# monitor.net
KiCad netlist of a schematic drawn in EAGLE
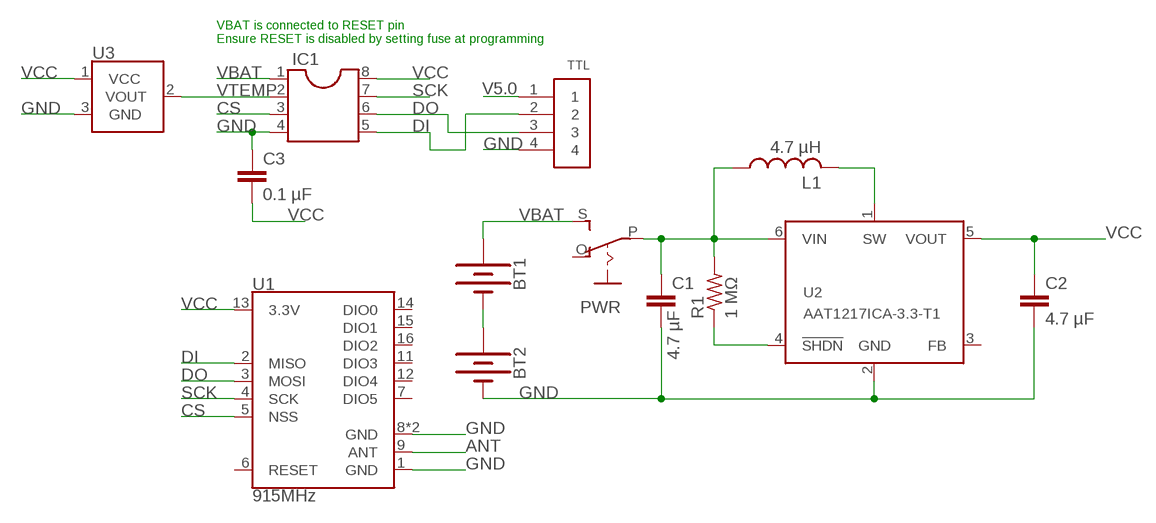
[diagram p0: schematic, sheet 1]

(export (version "E")
  (design (tool "Eeschema 10.0.6"))
  (components
    (comp (ref "BT1")
      (value "BATTERY-AA")
      (footprint "eagle-import:BATTERY-AA")
      (libsource (lib "eagle-import") (part "BATTERY-AA"))
    )
    (comp (ref "BT2")
      (value "BATTERY-AA")
      (footprint "eagle-import:BATTERY-AA")
      (libsource (lib "eagle-import") (part "BATTERY-AA"))
    )
    (comp (ref "C1")
      (value "4.7 µF")
      (footprint "eagle-import:C025-025X050")
      (libsource (lib "eagle-import") (part "C-EU025-025X050"))
    )
    (comp (ref "C2")
      (value "4.7 µF")
      (footprint "eagle-import:C025-025X050")
      (libsource (lib "eagle-import") (part "C-EU025-025X050"))
    )
    (comp (ref "C3")
      (value "0.1 µF")
      (footprint "eagle-import:C025-025X050")
      (libsource (lib "eagle-import") (part "C-EU025-025X050"))
    )
    (comp (ref "IC1")
      (value "DIL8S")
      (footprint "eagle-import:SOCKET-08")
      (libsource (lib "eagle-import") (part "DIL8S"))
    )
    (comp (ref "L1")
      (value "4.7 µH")
      (footprint "eagle-import:0207_12")
      (libsource (lib "eagle-import") (part "L-US0207/12"))
    )
    (comp (ref "PWR")
      (value "EG1218S")
      (footprint "eagle-import:EG1218")
      (libsource (lib "eagle-import") (part "EG1218S"))
    )
    (comp (ref "R1")
      (value "1 MΩ")
      (footprint "eagle-import:0204_5")
      (libsource (lib "eagle-import") (part "R-US_0204/5"))
    )
    (comp (ref "TTL")
      (value "1X4-BIG")
      (footprint "eagle-import:1X04-BIG")
      (libsource (lib "eagle-import") (part "1X4-BIG"))
    )
    (comp (ref "U1")
      (value "915MHz")
      (footprint "eagle-import:RFM69HCW-XXXS2")
      (libsource (lib "eagle-import") (part "RFM69HCW-915"))
    )
    (comp (ref "U2")
      (value "AAT1217ICA-3.3-T1")
      (footprint "eagle-import:TSOT-23-6")
      (libsource (lib "eagle-import") (part "AAT1217ICA-3.3-T1"))
    )
    (comp (ref "U3")
      (value "TMP36GT9")
      (footprint "eagle-import:TO-92")
      (libsource (lib "eagle-import") (part "TMP36GT9"))
    )
  )
  (nets
    (net (code "1") (name "/ANT") (class "Default")
      (node (ref "U1") (pin "9") (pinfunction "ANT_9") (pintype "passive"))
    )
    (net (code "2") (name "/CS") (class "Default")
      (node (ref "IC1") (pin "3") (pinfunction "3_3") (pintype "passive"))
      (node (ref "U1") (pin "5") (pinfunction "NSS_5") (pintype "input"))
    )
    (net (code "3") (name "/DI") (class "Default")
      (node (ref "IC1") (pin "5") (pinfunction "5_5") (pintype "passive"))
      (node (ref "TTL") (pin "2") (pinfunction "2_2") (pintype "bidirectional"))
      (node (ref "U1") (pin "2") (pinfunction "MISO_2") (pintype "bidirectional"))
    )
    (net (code "4") (name "/DO") (class "Default")
      (node (ref "IC1") (pin "6") (pinfunction "6_6") (pintype "passive"))
      (node (ref "TTL") (pin "3") (pinfunction "3_3") (pintype "bidirectional"))
      (node (ref "U1") (pin "3") (pinfunction "MOSI_3") (pintype "input"))
    )
    (net (code "5") (name "/GND") (class "Default")
      (node (ref "BT2") (pin "GND@1") (pinfunction "-_GND@1") (pintype "power_in"))
      (node (ref "C1") (pin "2") (pinfunction "2_2") (pintype "passive"))
      (node (ref "C2") (pin "2") (pinfunction "2_2") (pintype "passive"))
      (node (ref "C3") (pin "1") (pinfunction "1_1") (pintype "passive"))
      (node (ref "IC1") (pin "4") (pinfunction "4_4") (pintype "passive"))
      (node (ref "TTL") (pin "4") (pinfunction "4_4") (pintype "bidirectional"))
      (node (ref "U1") (pin "1") (pinfunction "GND_1") (pintype "power_in"))
      (node (ref "U1") (pin "10") (pinfunction "GND_10") (pintype "power_in"))
      (node (ref "U1") (pin "8") (pinfunction "GND_8") (pintype "power_in"))
      (node (ref "U2") (pin "2") (pinfunction "GND_2") (pintype "bidirectional"))
      (node (ref "U3") (pin "3") (pinfunction "GND_3") (pintype "bidirectional"))
    )
    (net (code "6") (name "/SCK") (class "Default")
      (node (ref "IC1") (pin "7") (pinfunction "7_7") (pintype "passive"))
      (node (ref "U1") (pin "4") (pinfunction "SCK_4") (pintype "input"))
    )
    (net (code "7") (name "/V5.0") (class "Default")
      (node (ref "TTL") (pin "1") (pinfunction "1_1") (pintype "bidirectional"))
    )
    (net (code "8") (name "/VBAT") (class "Default")
      (node (ref "C1") (pin "1") (pinfunction "1_1") (pintype "passive"))
      (node (ref "IC1") (pin "1") (pinfunction "1_1") (pintype "passive"))
      (node (ref "L1") (pin "1") (pinfunction "1_1") (pintype "passive"))
      (node (ref "PWR") (pin "P") (pinfunction "P_P") (pintype "passive"))
      (node (ref "R1") (pin "2") (pinfunction "2_2") (pintype "passive"))
      (node (ref "U2") (pin "6") (pinfunction "VIN_6") (pintype "bidirectional"))
    )
    (net (code "9") (name "/VCC") (class "Default")
      (node (ref "C2") (pin "1") (pinfunction "1_1") (pintype "passive"))
      (node (ref "C3") (pin "2") (pinfunction "2_2") (pintype "passive"))
      (node (ref "IC1") (pin "8") (pinfunction "8_8") (pintype "passive"))
      (node (ref "U1") (pin "13") (pinfunction "3.3V_13") (pintype "power_in"))
      (node (ref "U2") (pin "5") (pinfunction "VOUT_5") (pintype "bidirectional"))
      (node (ref "U3") (pin "1") (pinfunction "VCC_1") (pintype "bidirectional"))
    )
    (net (code "10") (name "/VTEMP") (class "Default")
      (node (ref "IC1") (pin "2") (pinfunction "2_2") (pintype "passive"))
      (node (ref "U3") (pin "2") (pinfunction "VOUT_2") (pintype "bidirectional"))
    )
    (net (code "11") (name "Net-(BT1-+)") (class "Default")
      (node (ref "BT1") (pin "PWR@1") (pinfunction "+_PWR@1") (pintype "power_in"))
      (node (ref "PWR") (pin "S") (pinfunction "S_S") (pintype "passive"))
    )
    (net (code "12") (name "Net-(BT1--)") (class "Default")
      (node (ref "BT1") (pin "GND@1") (pinfunction "-_GND@1") (pintype "power_in"))
      (node (ref "BT2") (pin "PWR@1") (pinfunction "+_PWR@1") (pintype "power_in"))
    )
    (net (code "13") (name "Net-(U2-SW)") (class "Default")
      (node (ref "L1") (pin "2") (pinfunction "2_2") (pintype "passive"))
      (node (ref "U2") (pin "1") (pinfunction "SW_1") (pintype "bidirectional"))
    )
    (net (code "14") (name "Net-(U2-~{SHDN})") (class "Default")
      (node (ref "R1") (pin "1") (pinfunction "1_1") (pintype "passive"))
      (node (ref "U2") (pin "4") (pinfunction "~{SHDN}_4") (pintype "bidirectional"))
    )
    (net (code "15") (name "unconnected-(PWR-PadO)") (class "Default")
      (node (ref "PWR") (pin "O") (pinfunction "O_O") (pintype "passive"))
    )
    (net (code "16") (name "unconnected-(U1-DIO0-Pad14)") (class "Default")
      (node (ref "U1") (pin "14") (pinfunction "DIO0_14") (pintype "bidirectional"))
    )
    (net (code "17") (name "unconnected-(U1-DIO1-Pad15)") (class "Default")
      (node (ref "U1") (pin "15") (pinfunction "DIO1_15") (pintype "bidirectional"))
    )
    (net (code "18") (name "unconnected-(U1-DIO2-Pad16)") (class "Default")
      (node (ref "U1") (pin "16") (pinfunction "DIO2_16") (pintype "bidirectional"))
    )
    (net (code "19") (name "unconnected-(U1-DIO3-Pad11)") (class "Default")
      (node (ref "U1") (pin "11") (pinfunction "DIO3_11") (pintype "bidirectional"))
    )
    (net (code "20") (name "unconnected-(U1-DIO4-Pad12)") (class "Default")
      (node (ref "U1") (pin "12") (pinfunction "DIO4_12") (pintype "bidirectional"))
    )
    (net (code "21") (name "unconnected-(U1-DIO5-Pad7)") (class "Default")
      (node (ref "U1") (pin "7") (pinfunction "DIO5_7") (pintype "bidirectional"))
    )
    (net (code "22") (name "unconnected-(U1-RESET-Pad6)") (class "Default")
      (node (ref "U1") (pin "6") (pinfunction "RESET_6") (pintype "input"))
    )
    (net (code "23") (name "unconnected-(U2-FB-Pad3)") (class "Default")
      (node (ref "U2") (pin "3") (pinfunction "FB_3") (pintype "bidirectional"))
    )
  )
)
